# MCB-MTS-Dragonfly-v2_0_0.net
KiCad netlist of a schematic drawn in EAGLE
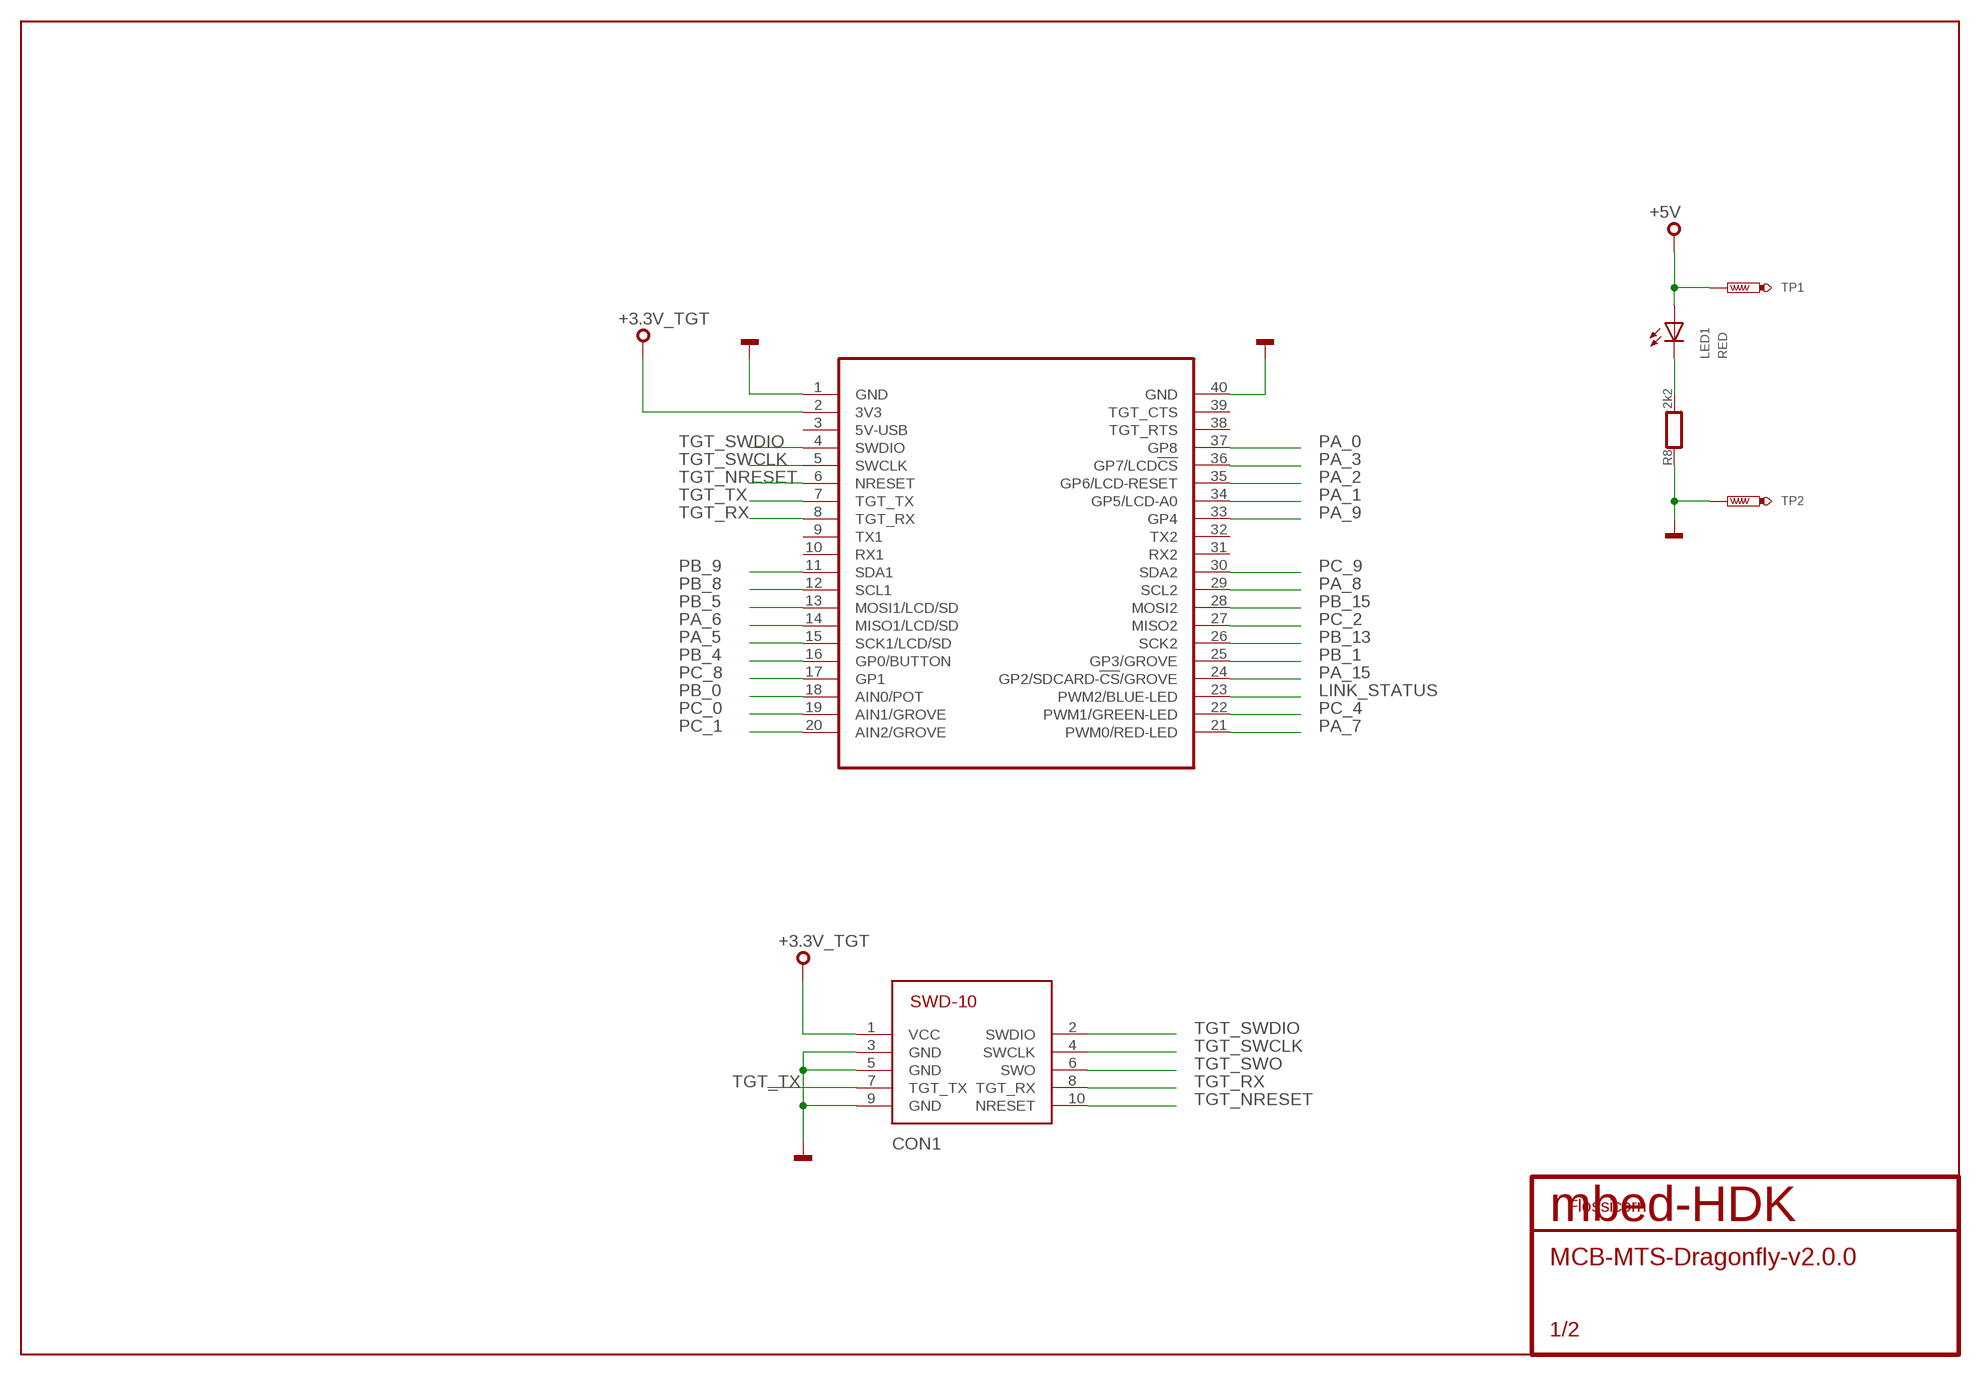
[diagram p0: schematic, sheet 1]
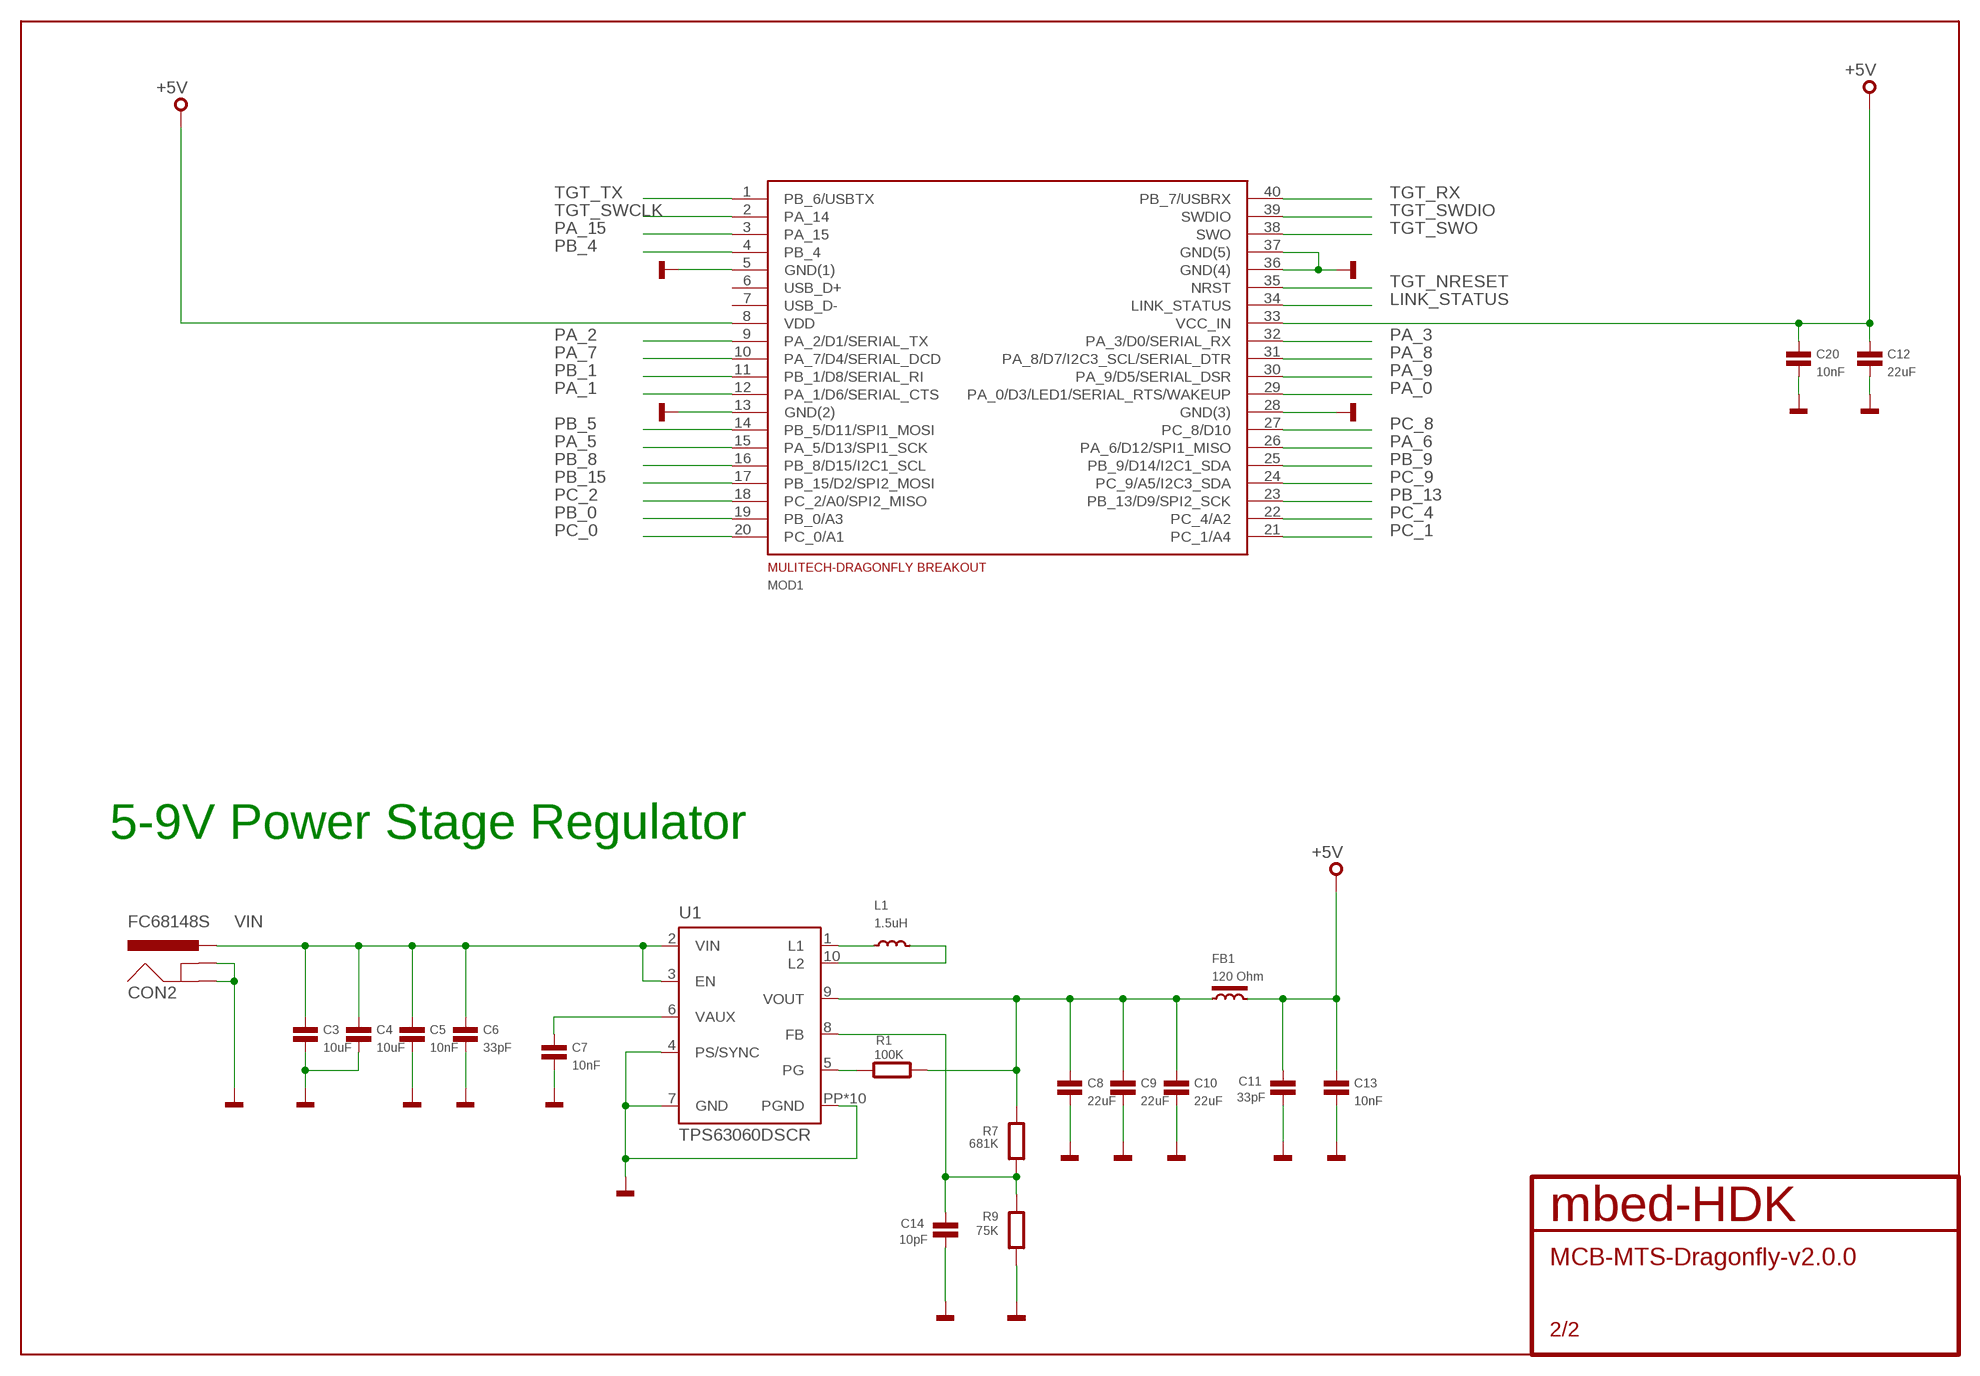
[diagram p1: schematic, sheet 2]

(export (version "E")
  (design (tool "Eeschema 10.0.6"))
  (components
    (comp (ref "CON1")
      (value "SWD-10/TC2050_SMD")
      (footprint "eagle-import:FTSH-105-02")
      (libsource (lib "eagle-import") (part "SWD-10/TC2050_SMD"))
    )
    (comp (ref "LED1")
      (value "RED")
      (footprint "eagle-import:CHIPLED_0603")
      (fields (field (name "MF") "Wurth Electronics Inc"))
      (libsource (lib "eagle-import") (part "SMD_LED0603"))
    )
    (comp (ref "MOD2")
      (value "MODULE_DAUGHTER")
      (footprint "eagle-import:MODULE_DAUGHTER")
      (libsource (lib "eagle-import") (part "MODULE_DAUGHTER"))
    )
    (comp (ref "R8")
      (value "2k2")
      (footprint "eagle-import:0603")
      (libsource (lib "eagle-import") (part "RESISTOR0603"))
    )
    (comp (ref "SS1")
      (value "FLOSSICORN0.5")
      (footprint "eagle-import:FLOSSICORN-0.5")
      (libsource (lib "eagle-import") (part "FLOSSICORN0.5"))
    )
    (comp (ref "TP1")
      (value "TEST-POINT-50R-PTH")
      (footprint "eagle-import:TP50-PTH")
      (libsource (lib "eagle-import") (part "TEST-POINT-50R-PTH"))
    )
    (comp (ref "TP2")
      (value "TEST-POINT-50R-PTH")
      (footprint "eagle-import:TP50-PTH")
      (libsource (lib "eagle-import") (part "TEST-POINT-50R-PTH"))
    )
    (comp (ref "C3")
      (value "10uF")
      (footprint "eagle-import:0603")
      (libsource (lib "eagle-import") (part "CAPACITOR0603"))
    )
    (comp (ref "C4")
      (value "10uF")
      (footprint "eagle-import:0603")
      (libsource (lib "eagle-import") (part "CAPACITOR0603"))
    )
    (comp (ref "C5")
      (value "10nF")
      (footprint "eagle-import:0603")
      (libsource (lib "eagle-import") (part "CAPACITOR0603"))
    )
    (comp (ref "C6")
      (value "33pF")
      (footprint "eagle-import:0603")
      (libsource (lib "eagle-import") (part "CAPACITOR0603"))
    )
    (comp (ref "C7")
      (value "10nF")
      (footprint "eagle-import:0603")
      (libsource (lib "eagle-import") (part "CAPACITOR0603"))
    )
    (comp (ref "C8")
      (value "22uF")
      (footprint "eagle-import:0603")
      (libsource (lib "eagle-import") (part "CAPACITOR0603"))
    )
    (comp (ref "C9")
      (value "22uF")
      (footprint "eagle-import:0603")
      (libsource (lib "eagle-import") (part "CAPACITOR0603"))
    )
    (comp (ref "C10")
      (value "22uF")
      (footprint "eagle-import:0603")
      (libsource (lib "eagle-import") (part "CAPACITOR0603"))
    )
    (comp (ref "C11")
      (value "33pF")
      (footprint "eagle-import:0603")
      (libsource (lib "eagle-import") (part "CAPACITOR0603"))
    )
    (comp (ref "C12")
      (value "22uF")
      (footprint "eagle-import:0603")
      (libsource (lib "eagle-import") (part "CAPACITOR0603"))
    )
    (comp (ref "C13")
      (value "10nF")
      (footprint "eagle-import:0603")
      (libsource (lib "eagle-import") (part "CAPACITOR0603"))
    )
    (comp (ref "C14")
      (value "10pF")
      (footprint "eagle-import:0603")
      (libsource (lib "eagle-import") (part "CAPACITOR0603"))
    )
    (comp (ref "C20")
      (value "10nF")
      (footprint "eagle-import:0603")
      (libsource (lib "eagle-import") (part "CAPACITOR0603"))
    )
    (comp (ref "CON2")
      (value "FC68148S")
      (footprint "eagle-import:FC68148S")
      (libsource (lib "eagle-import") (part "FC68148S"))
    )
    (comp (ref "FB1")
      (value "120 Ohm")
      (footprint "eagle-import:0603")
      (libsource (lib "eagle-import") (part "FERRITE0603"))
    )
    (comp (ref "L1")
      (value "1.5uH")
      (footprint "eagle-import:XFL4020-472MEC")
      (libsource (lib "eagle-import") (part "INDUCTORXFL4020"))
    )
    (comp (ref "MOD1")
      (value "MULITECH-DRAGONFLY-BREAKOUT")
      (footprint "eagle-import:MULITECH-DRAGONFLY-BREAKOUT")
      (fields (field (name "MF") "Hirose"))
      (libsource (lib "eagle-import") (part "MULITECH-DRAGONFLY-BREAKOUT"))
    )
    (comp (ref "R1")
      (value "100K")
      (footprint "eagle-import:0402")
      (libsource (lib "eagle-import") (part "mbed-HDK-RLCQ_RESISTOR0402"))
    )
    (comp (ref "R7")
      (value "681K")
      (footprint "eagle-import:0402")
      (libsource (lib "eagle-import") (part "mbed-HDK-RLCQ_RESISTOR0402"))
    )
    (comp (ref "R9")
      (value "75K")
      (footprint "eagle-import:0402")
      (libsource (lib "eagle-import") (part "mbed-HDK-RLCQ_RESISTOR0402"))
    )
    (comp (ref "U1")
      (value "TPS63060DSCR")
      (footprint "eagle-import:DSC-S-PWSON-N10")
      (fields (field (name "MF") "TEXAS INSTRUMENTS"))
      (libsource (lib "eagle-import") (part "TPS63060DSCR"))
    )
  )
  (nets
    (net (code "1") (name "+3.3V_TGT") (class "Default")
      (node (ref "CON1") (pin "1") (pinfunction "VCC_1") (pintype "bidirectional"))
      (node (ref "MOD2") (pin "2") (pinfunction "3V3_2") (pintype "bidirectional"))
    )
    (net (code "2") (name "+5V") (class "Default")
      (node (ref "C11") (pin "1") (pinfunction "P$1_1") (pintype "passive"))
      (node (ref "C12") (pin "1") (pinfunction "P$1_1") (pintype "passive"))
      (node (ref "C13") (pin "1") (pinfunction "P$1_1") (pintype "passive"))
      (node (ref "C20") (pin "1") (pinfunction "P$1_1") (pintype "passive"))
      (node (ref "FB1") (pin "2") (pinfunction "P$2_2") (pintype "bidirectional"))
      (node (ref "LED1") (pin "A") (pinfunction "A_A") (pintype "passive"))
      (node (ref "MOD1") (pin "33") (pinfunction "VCC_IN_33") (pintype "bidirectional"))
      (node (ref "MOD1") (pin "8") (pinfunction "VDD_8") (pintype "bidirectional"))
      (node (ref "TP1") (pin "TP") (pinfunction "TP_TP") (pintype "input"))
    )
    (net (code "3") (name "GND") (class "Default")
      (node (ref "C10") (pin "2") (pinfunction "P$2_2") (pintype "passive"))
      (node (ref "C11") (pin "2") (pinfunction "P$2_2") (pintype "passive"))
      (node (ref "C12") (pin "2") (pinfunction "P$2_2") (pintype "passive"))
      (node (ref "C13") (pin "2") (pinfunction "P$2_2") (pintype "passive"))
      (node (ref "C14") (pin "2") (pinfunction "P$2_2") (pintype "passive"))
      (node (ref "C20") (pin "2") (pinfunction "P$2_2") (pintype "passive"))
      (node (ref "C3") (pin "2") (pinfunction "P$2_2") (pintype "passive"))
      (node (ref "C4") (pin "2") (pinfunction "P$2_2") (pintype "passive"))
      (node (ref "C5") (pin "2") (pinfunction "P$2_2") (pintype "passive"))
      (node (ref "C6") (pin "2") (pinfunction "P$2_2") (pintype "passive"))
      (node (ref "C7") (pin "2") (pinfunction "P$2_2") (pintype "passive"))
      (node (ref "C8") (pin "2") (pinfunction "P$2_2") (pintype "passive"))
      (node (ref "C9") (pin "2") (pinfunction "P$2_2") (pintype "passive"))
      (node (ref "CON1") (pin "3") (pinfunction "GND_3") (pintype "bidirectional"))
      (node (ref "CON1") (pin "5") (pinfunction "GND_5") (pintype "bidirectional"))
      (node (ref "CON1") (pin "9") (pinfunction "GND_9") (pintype "bidirectional"))
      (node (ref "CON2") (pin "2") (pinfunction "GNDBREAK_2") (pintype "bidirectional"))
      (node (ref "CON2") (pin "3") (pinfunction "GND_3") (pintype "bidirectional"))
      (node (ref "MOD1") (pin "13") (pinfunction "GND(2)_13") (pintype "bidirectional"))
      (node (ref "MOD1") (pin "28") (pinfunction "GND(3)_28") (pintype "bidirectional"))
      (node (ref "MOD1") (pin "36") (pinfunction "GND(4)_36") (pintype "bidirectional"))
      (node (ref "MOD1") (pin "37") (pinfunction "GND(5)_37") (pintype "bidirectional"))
      (node (ref "MOD1") (pin "5") (pinfunction "GND(1)_5") (pintype "bidirectional"))
      (node (ref "MOD2") (pin "1") (pinfunction "GND_1") (pintype "bidirectional"))
      (node (ref "MOD2") (pin "40") (pinfunction "GND_40") (pintype "bidirectional"))
      (node (ref "R8") (pin "1") (pinfunction "P$1_1") (pintype "passive"))
      (node (ref "R9") (pin "1") (pinfunction "P$1_1") (pintype "passive"))
      (node (ref "TP2") (pin "TP") (pinfunction "TP_TP") (pintype "input"))
      (node (ref "U1") (pin "4") (pinfunction "PS/SYNC_4") (pintype "input"))
      (node (ref "U1") (pin "7") (pinfunction "GND_7") (pintype "input"))
      (node (ref "U1") (pin "PP") (pinfunction "PGND_PP") (pintype "power_in"))
      (node (ref "U1") (pin "PP@1") (pinfunction "PGND_PP@1") (pintype "power_in"))
      (node (ref "U1") (pin "PP@10") (pinfunction "PGND_PP@10") (pintype "power_in"))
      (node (ref "U1") (pin "PP@2") (pinfunction "PGND_PP@2") (pintype "power_in"))
      (node (ref "U1") (pin "PP@3") (pinfunction "PGND_PP@3") (pintype "power_in"))
      (node (ref "U1") (pin "PP@4") (pinfunction "PGND_PP@4") (pintype "power_in"))
      (node (ref "U1") (pin "PP@5") (pinfunction "PGND_PP@5") (pintype "power_in"))
      (node (ref "U1") (pin "PP@7") (pinfunction "PGND_PP@7") (pintype "power_in"))
      (node (ref "U1") (pin "PP@8") (pinfunction "PGND_PP@8") (pintype "power_in"))
      (node (ref "U1") (pin "PP@9") (pinfunction "PGND_PP@9") (pintype "power_in"))
    )
    (net (code "4") (name "LINK_STATUS") (class "Default")
      (node (ref "MOD1") (pin "34") (pinfunction "LINK_STATUS_34") (pintype "bidirectional"))
      (node (ref "MOD2") (pin "23") (pinfunction "PWM2/BLUE-LED_23") (pintype "bidirectional"))
    )
    (net (code "5") (name "Net-(C7-P$1)") (class "Default")
      (node (ref "C7") (pin "1") (pinfunction "P$1_1") (pintype "passive"))
      (node (ref "U1") (pin "6") (pinfunction "VAUX_6") (pintype "power_in"))
    )
    (net (code "6") (name "Net-(C10-P$1)") (class "Default")
      (node (ref "C10") (pin "1") (pinfunction "P$1_1") (pintype "passive"))
      (node (ref "C8") (pin "1") (pinfunction "P$1_1") (pintype "passive"))
      (node (ref "C9") (pin "1") (pinfunction "P$1_1") (pintype "passive"))
      (node (ref "FB1") (pin "1") (pinfunction "P$1_1") (pintype "bidirectional"))
      (node (ref "R1") (pin "2") (pinfunction "P$2_2") (pintype "passive"))
      (node (ref "R7") (pin "2") (pinfunction "P$2_2") (pintype "passive"))
      (node (ref "U1") (pin "9") (pinfunction "VOUT_9") (pintype "output"))
    )
    (net (code "7") (name "Net-(C14-P$1)") (class "Default")
      (node (ref "C14") (pin "1") (pinfunction "P$1_1") (pintype "passive"))
      (node (ref "R7") (pin "1") (pinfunction "P$1_1") (pintype "passive"))
      (node (ref "R9") (pin "2") (pinfunction "P$2_2") (pintype "passive"))
      (node (ref "U1") (pin "8") (pinfunction "FB_8") (pintype "input"))
    )
    (net (code "8") (name "Net-(R1-P$1)") (class "Default")
      (node (ref "R1") (pin "1") (pinfunction "P$1_1") (pintype "passive"))
      (node (ref "U1") (pin "5") (pinfunction "PG_5") (pintype "output"))
    )
    (net (code "9") (name "Net-(R8-P$2)") (class "Default")
      (node (ref "LED1") (pin "C") (pinfunction "C_C") (pintype "passive"))
      (node (ref "R8") (pin "2") (pinfunction "P$2_2") (pintype "passive"))
    )
    (net (code "10") (name "Net-(U1-L1)") (class "Default")
      (node (ref "L1") (pin "P$1") (pinfunction "P$1_P$1") (pintype "bidirectional"))
      (node (ref "U1") (pin "1") (pinfunction "L1_1") (pintype "input"))
    )
    (net (code "11") (name "Net-(U1-L2)") (class "Default")
      (node (ref "L1") (pin "P$2") (pinfunction "P$2_P$2") (pintype "bidirectional"))
      (node (ref "U1") (pin "10") (pinfunction "L2_10") (pintype "input"))
    )
    (net (code "12") (name "PA_0") (class "Default")
      (node (ref "MOD1") (pin "29") (pinfunction "PA_0/D3/LED1/SERIAL_RTS/WAKEUP_29") (pintype "bidirectional"))
      (node (ref "MOD2") (pin "37") (pinfunction "GP8_37") (pintype "bidirectional"))
    )
    (net (code "13") (name "PA_1") (class "Default")
      (node (ref "MOD1") (pin "12") (pinfunction "PA_1/D6/SERIAL_CTS_12") (pintype "bidirectional"))
      (node (ref "MOD2") (pin "34") (pinfunction "GP5/LCD-A0_34") (pintype "bidirectional"))
    )
    (net (code "14") (name "PA_2") (class "Default")
      (node (ref "MOD1") (pin "9") (pinfunction "PA_2/D1/SERIAL_TX_9") (pintype "bidirectional"))
      (node (ref "MOD2") (pin "35") (pinfunction "GP6/LCD-RESET_35") (pintype "bidirectional"))
    )
    (net (code "15") (name "PA_3") (class "Default")
      (node (ref "MOD1") (pin "32") (pinfunction "PA_3/D0/SERIAL_RX_32") (pintype "bidirectional"))
      (node (ref "MOD2") (pin "36") (pinfunction "GP7/LCD~{CS}_36") (pintype "bidirectional"))
    )
    (net (code "16") (name "PA_5") (class "Default")
      (node (ref "MOD1") (pin "15") (pinfunction "PA_5/D13/SPI1_SCK_15") (pintype "bidirectional"))
      (node (ref "MOD2") (pin "15") (pinfunction "SCK1/LCD/SD_15") (pintype "bidirectional"))
    )
    (net (code "17") (name "PA_6") (class "Default")
      (node (ref "MOD1") (pin "26") (pinfunction "PA_6/D12/SPI1_MISO_26") (pintype "bidirectional"))
      (node (ref "MOD2") (pin "14") (pinfunction "MISO1/LCD/SD_14") (pintype "bidirectional"))
    )
    (net (code "18") (name "PA_7") (class "Default")
      (node (ref "MOD1") (pin "10") (pinfunction "PA_7/D4/SERIAL_DCD_10") (pintype "bidirectional"))
      (node (ref "MOD2") (pin "21") (pinfunction "PWM0/RED-LED_21") (pintype "bidirectional"))
    )
    (net (code "19") (name "PA_8") (class "Default")
      (node (ref "MOD1") (pin "31") (pinfunction "PA_8/D7/I2C3_SCL/SERIAL_DTR_31") (pintype "bidirectional"))
      (node (ref "MOD2") (pin "29") (pinfunction "SCL2_29") (pintype "bidirectional"))
    )
    (net (code "20") (name "PA_9") (class "Default")
      (node (ref "MOD1") (pin "30") (pinfunction "PA_9/D5/SERIAL_DSR_30") (pintype "bidirectional"))
      (node (ref "MOD2") (pin "33") (pinfunction "GP4_33") (pintype "bidirectional"))
    )
    (net (code "21") (name "PA_15") (class "Default")
      (node (ref "MOD1") (pin "3") (pinfunction "PA_15_3") (pintype "bidirectional"))
      (node (ref "MOD2") (pin "24") (pinfunction "GP2/SDCARD-~{CS}/GROVE_24") (pintype "bidirectional"))
    )
    (net (code "22") (name "PB_0") (class "Default")
      (node (ref "MOD1") (pin "19") (pinfunction "PB_0/A3_19") (pintype "bidirectional"))
      (node (ref "MOD2") (pin "18") (pinfunction "AIN0/POT_18") (pintype "bidirectional"))
    )
    (net (code "23") (name "PB_1") (class "Default")
      (node (ref "MOD1") (pin "11") (pinfunction "PB_1/D8/SERIAL_RI_11") (pintype "bidirectional"))
      (node (ref "MOD2") (pin "25") (pinfunction "GP3/GROVE_25") (pintype "bidirectional"))
    )
    (net (code "24") (name "PB_4") (class "Default")
      (node (ref "MOD1") (pin "4") (pinfunction "PB_4_4") (pintype "bidirectional"))
      (node (ref "MOD2") (pin "16") (pinfunction "GP0/BUTTON_16") (pintype "bidirectional"))
    )
    (net (code "25") (name "PB_5") (class "Default")
      (node (ref "MOD1") (pin "14") (pinfunction "PB_5/D11/SPI1_MOSI_14") (pintype "bidirectional"))
      (node (ref "MOD2") (pin "13") (pinfunction "MOSI1/LCD/SD_13") (pintype "bidirectional"))
    )
    (net (code "26") (name "PB_8") (class "Default")
      (node (ref "MOD1") (pin "16") (pinfunction "PB_8/D15/I2C1_SCL_16") (pintype "bidirectional"))
      (node (ref "MOD2") (pin "12") (pinfunction "SCL1_12") (pintype "bidirectional"))
    )
    (net (code "27") (name "PB_9") (class "Default")
      (node (ref "MOD1") (pin "25") (pinfunction "PB_9/D14/I2C1_SDA_25") (pintype "bidirectional"))
      (node (ref "MOD2") (pin "11") (pinfunction "SDA1_11") (pintype "bidirectional"))
    )
    (net (code "28") (name "PB_13") (class "Default")
      (node (ref "MOD1") (pin "23") (pinfunction "PB_13/D9/SPI2_SCK_23") (pintype "bidirectional"))
      (node (ref "MOD2") (pin "26") (pinfunction "SCK2_26") (pintype "bidirectional"))
    )
    (net (code "29") (name "PB_15") (class "Default")
      (node (ref "MOD1") (pin "17") (pinfunction "PB_15/D2/SPI2_MOSI_17") (pintype "bidirectional"))
      (node (ref "MOD2") (pin "28") (pinfunction "MOSI2_28") (pintype "bidirectional"))
    )
    (net (code "30") (name "PC_0") (class "Default")
      (node (ref "MOD1") (pin "20") (pinfunction "PC_0/A1_20") (pintype "bidirectional"))
      (node (ref "MOD2") (pin "19") (pinfunction "AIN1/GROVE_19") (pintype "bidirectional"))
    )
    (net (code "31") (name "PC_1") (class "Default")
      (node (ref "MOD1") (pin "21") (pinfunction "PC_1/A4_21") (pintype "bidirectional"))
      (node (ref "MOD2") (pin "20") (pinfunction "AIN2/GROVE_20") (pintype "bidirectional"))
    )
    (net (code "32") (name "PC_2") (class "Default")
      (node (ref "MOD1") (pin "18") (pinfunction "PC_2/A0/SPI2_MISO_18") (pintype "bidirectional"))
      (node (ref "MOD2") (pin "27") (pinfunction "MISO2_27") (pintype "bidirectional"))
    )
    (net (code "33") (name "PC_4") (class "Default")
      (node (ref "MOD1") (pin "22") (pinfunction "PC_4/A2_22") (pintype "bidirectional"))
      (node (ref "MOD2") (pin "22") (pinfunction "PWM1/GREEN-LED_22") (pintype "bidirectional"))
    )
    (net (code "34") (name "PC_8") (class "Default")
      (node (ref "MOD1") (pin "27") (pinfunction "PC_8/D10_27") (pintype "bidirectional"))
      (node (ref "MOD2") (pin "17") (pinfunction "GP1_17") (pintype "bidirectional"))
    )
    (net (code "35") (name "PC_9") (class "Default")
      (node (ref "MOD1") (pin "24") (pinfunction "PC_9/A5/I2C3_SDA_24") (pintype "bidirectional"))
      (node (ref "MOD2") (pin "30") (pinfunction "SDA2_30") (pintype "bidirectional"))
    )
    (net (code "36") (name "TGT_NRESET") (class "Default")
      (node (ref "CON1") (pin "10") (pinfunction "NRESET_10") (pintype "bidirectional"))
      (node (ref "MOD1") (pin "35") (pinfunction "NRST_35") (pintype "bidirectional"))
      (node (ref "MOD2") (pin "6") (pinfunction "NRESET_6") (pintype "bidirectional"))
    )
    (net (code "37") (name "TGT_RX") (class "Default")
      (node (ref "CON1") (pin "8") (pinfunction "TGT_RX_8") (pintype "bidirectional"))
      (node (ref "MOD1") (pin "40") (pinfunction "PB_7/USBRX_40") (pintype "bidirectional"))
      (node (ref "MOD2") (pin "8") (pinfunction "TGT_RX_8") (pintype "bidirectional"))
    )
    (net (code "38") (name "TGT_SWCLK") (class "Default")
      (node (ref "CON1") (pin "4") (pinfunction "SWCLK_4") (pintype "bidirectional"))
      (node (ref "MOD1") (pin "2") (pinfunction "PA_14_2") (pintype "bidirectional"))
      (node (ref "MOD2") (pin "5") (pinfunction "SWCLK_5") (pintype "bidirectional"))
    )
    (net (code "39") (name "TGT_SWDIO") (class "Default")
      (node (ref "CON1") (pin "2") (pinfunction "SWDIO_2") (pintype "bidirectional"))
      (node (ref "MOD1") (pin "39") (pinfunction "SWDIO_39") (pintype "bidirectional"))
      (node (ref "MOD2") (pin "4") (pinfunction "SWDIO_4") (pintype "bidirectional"))
    )
    (net (code "40") (name "TGT_SWO") (class "Default")
      (node (ref "CON1") (pin "6") (pinfunction "SWO_6") (pintype "bidirectional"))
      (node (ref "MOD1") (pin "38") (pinfunction "SWO_38") (pintype "bidirectional"))
    )
    (net (code "41") (name "TGT_TX") (class "Default")
      (node (ref "CON1") (pin "7") (pinfunction "TGT_TX_7") (pintype "bidirectional"))
      (node (ref "MOD1") (pin "1") (pinfunction "PB_6/USBTX_1") (pintype "bidirectional"))
      (node (ref "MOD2") (pin "7") (pinfunction "TGT_TX_7") (pintype "bidirectional"))
    )
    (net (code "42") (name "VIN") (class "Default")
      (node (ref "C3") (pin "1") (pinfunction "P$1_1") (pintype "passive"))
      (node (ref "C4") (pin "1") (pinfunction "P$1_1") (pintype "passive"))
      (node (ref "C5") (pin "1") (pinfunction "P$1_1") (pintype "passive"))
      (node (ref "C6") (pin "1") (pinfunction "P$1_1") (pintype "passive"))
      (node (ref "CON2") (pin "1-1") (pinfunction "PWR_1-1") (pintype "bidirectional"))
      (node (ref "CON2") (pin "1-2") (pinfunction "PWR_1-2") (pintype "bidirectional"))
      (node (ref "U1") (pin "2") (pinfunction "VIN_2") (pintype "input"))
      (node (ref "U1") (pin "3") (pinfunction "EN_3") (pintype "input"))
    )
    (net (code "43") (name "unconnected-(MOD1-USB_D+-Pad6)") (class "Default")
      (node (ref "MOD1") (pin "6") (pinfunction "USB_D+_6") (pintype "bidirectional"))
    )
    (net (code "44") (name "unconnected-(MOD1-USB_D--Pad7)") (class "Default")
      (node (ref "MOD1") (pin "7") (pinfunction "USB_D-_7") (pintype "bidirectional"))
    )
    (net (code "45") (name "unconnected-(MOD2-5V-USB-Pad3)") (class "Default")
      (node (ref "MOD2") (pin "3") (pinfunction "5V-USB_3") (pintype "bidirectional"))
    )
    (net (code "46") (name "unconnected-(MOD2-RX1-Pad10)") (class "Default")
      (node (ref "MOD2") (pin "10") (pinfunction "RX1_10") (pintype "bidirectional"))
    )
    (net (code "47") (name "unconnected-(MOD2-RX2-Pad31)") (class "Default")
      (node (ref "MOD2") (pin "31") (pinfunction "RX2_31") (pintype "bidirectional"))
    )
    (net (code "48") (name "unconnected-(MOD2-TGT_CTS-Pad39)") (class "Default")
      (node (ref "MOD2") (pin "39") (pinfunction "TGT_CTS_39") (pintype "bidirectional"))
    )
    (net (code "49") (name "unconnected-(MOD2-TGT_RTS-Pad38)") (class "Default")
      (node (ref "MOD2") (pin "38") (pinfunction "TGT_RTS_38") (pintype "bidirectional"))
    )
    (net (code "50") (name "unconnected-(MOD2-TX1-Pad9)") (class "Default")
      (node (ref "MOD2") (pin "9") (pinfunction "TX1_9") (pintype "bidirectional"))
    )
    (net (code "51") (name "unconnected-(MOD2-TX2-Pad32)") (class "Default")
      (node (ref "MOD2") (pin "32") (pinfunction "TX2_32") (pintype "bidirectional"))
    )
  )
)
